# 05_MOTORS.net
KiCad netlist of a schematic drawn in Altium Designer
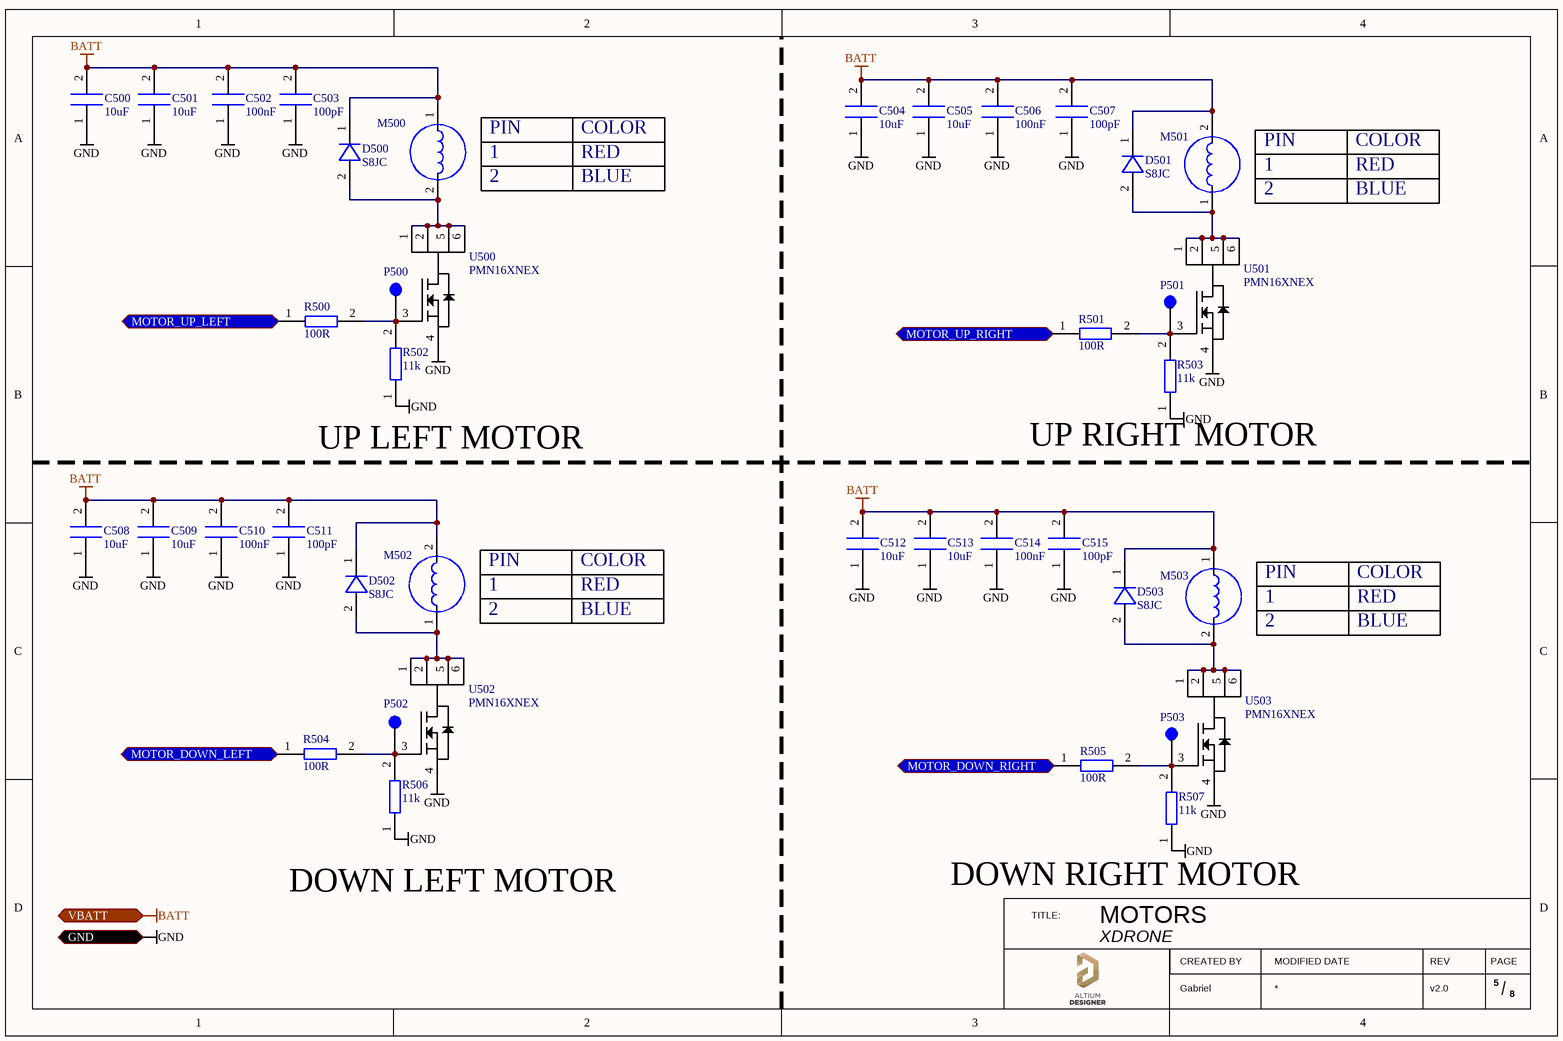
[diagram p0: 05_MOTORS.SchDoc]

(export (version "E")
  (design (tool "Eeschema 10.0.6"))
  (components
    (comp (ref "C500")
      (value "10uF")
      (footprint "CAP_0805")
      (description "CAP 10uF 10% 10V 0805 X6S")
      (fields (field (name "TOLERANCE") "10%") (field (name "MANUFACTURER") "MURATA"))
      (libsource (lib "Capacitors") (part "10uF_10%_10V_0805_X6S_GRM21BC81C106KA73L"))
    )
    (comp (ref "C501")
      (value "10uF")
      (footprint "CAP_0805")
      (description "CAP 10uF 10% 10V 0805 X6S")
      (fields (field (name "TOLERANCE") "10%") (field (name "MANUFACTURER") "MURATA"))
      (libsource (lib "Capacitors") (part "10uF_10%_10V_0805_X6S_GRM21BC81C106KA73L"))
    )
    (comp (ref "C502")
      (value "100nF")
      (footprint "CAP_0402")
      (description "CAPACITOR 100nF 10% X7R 0402")
      (fields (field (name "TOLERANCE") "10%") (field (name "MANUFACTURER") "MURATA"))
      (libsource (lib "Capacitors") (part "100nF_10%_16V_0402_GRM155R71C104KA88J"))
    )
    (comp (ref "C503")
      (value "100pF")
      (footprint "CAP_0402")
      (description "CAPACITOR 100pF 5% 50V 0402 CC0402JRNPO9BN101")
      (fields (field (name "TOLERANCE") "5%") (field (name "MANUFACTURER") "YAGEO"))
      (libsource (lib "Capacitors") (part "100pF_5%_50V_0402_CC0402JRNPO9BN101"))
    )
    (comp (ref "C504")
      (value "10uF")
      (footprint "CAP_0805")
      (description "CAP 10uF 10% 10V 0805 X6S")
      (fields (field (name "TOLERANCE") "10%") (field (name "MANUFACTURER") "MURATA"))
      (libsource (lib "Capacitors") (part "10uF_10%_10V_0805_X6S_GRM21BC81C106KA73L"))
    )
    (comp (ref "C505")
      (value "10uF")
      (footprint "CAP_0805")
      (description "CAP 10uF 10% 10V 0805 X6S")
      (fields (field (name "TOLERANCE") "10%") (field (name "MANUFACTURER") "MURATA"))
      (libsource (lib "Capacitors") (part "10uF_10%_10V_0805_X6S_GRM21BC81C106KA73L"))
    )
    (comp (ref "C506")
      (value "100nF")
      (footprint "CAP_0402")
      (description "CAPACITOR 100nF 10% X7R 0402")
      (fields (field (name "TOLERANCE") "10%") (field (name "MANUFACTURER") "MURATA"))
      (libsource (lib "Capacitors") (part "100nF_10%_16V_0402_GRM155R71C104KA88J"))
    )
    (comp (ref "C507")
      (value "100pF")
      (footprint "CAP_0402")
      (description "CAPACITOR 100pF 5% 50V 0402 CC0402JRNPO9BN101")
      (fields (field (name "TOLERANCE") "5%") (field (name "MANUFACTURER") "YAGEO"))
      (libsource (lib "Capacitors") (part "100pF_5%_50V_0402_CC0402JRNPO9BN101"))
    )
    (comp (ref "C508")
      (value "10uF")
      (footprint "CAP_0805")
      (description "CAP 10uF 10% 10V 0805 X6S")
      (fields (field (name "TOLERANCE") "10%") (field (name "MANUFACTURER") "MURATA"))
      (libsource (lib "Capacitors") (part "10uF_10%_10V_0805_X6S_GRM21BC81C106KA73L"))
    )
    (comp (ref "C509")
      (value "10uF")
      (footprint "CAP_0805")
      (description "CAP 10uF 10% 10V 0805 X6S")
      (fields (field (name "TOLERANCE") "10%") (field (name "MANUFACTURER") "MURATA"))
      (libsource (lib "Capacitors") (part "10uF_10%_10V_0805_X6S_GRM21BC81C106KA73L"))
    )
    (comp (ref "C510")
      (value "100nF")
      (footprint "CAP_0402")
      (description "CAPACITOR 100nF 10% X7R 0402")
      (fields (field (name "TOLERANCE") "10%") (field (name "MANUFACTURER") "MURATA"))
      (libsource (lib "Capacitors") (part "100nF_10%_16V_0402_GRM155R71C104KA88J"))
    )
    (comp (ref "C511")
      (value "100pF")
      (footprint "CAP_0402")
      (description "CAPACITOR 100pF 5% 50V 0402 CC0402JRNPO9BN101")
      (fields (field (name "TOLERANCE") "5%") (field (name "MANUFACTURER") "YAGEO"))
      (libsource (lib "Capacitors") (part "100pF_5%_50V_0402_CC0402JRNPO9BN101"))
    )
    (comp (ref "C512")
      (value "10uF")
      (footprint "CAP_0805")
      (description "CAP 10uF 10% 10V 0805 X6S")
      (fields (field (name "TOLERANCE") "10%") (field (name "MANUFACTURER") "MURATA"))
      (libsource (lib "Capacitors") (part "10uF_10%_10V_0805_X6S_GRM21BC81C106KA73L"))
    )
    (comp (ref "C513")
      (value "10uF")
      (footprint "CAP_0805")
      (description "CAP 10uF 10% 10V 0805 X6S")
      (fields (field (name "TOLERANCE") "10%") (field (name "MANUFACTURER") "MURATA"))
      (libsource (lib "Capacitors") (part "10uF_10%_10V_0805_X6S_GRM21BC81C106KA73L"))
    )
    (comp (ref "C514")
      (value "100nF")
      (footprint "CAP_0402")
      (description "CAPACITOR 100nF 10% X7R 0402")
      (fields (field (name "TOLERANCE") "10%") (field (name "MANUFACTURER") "MURATA"))
      (libsource (lib "Capacitors") (part "100nF_10%_16V_0402_GRM155R71C104KA88J"))
    )
    (comp (ref "C515")
      (value "100pF")
      (footprint "CAP_0402")
      (description "CAPACITOR 100pF 5% 50V 0402 CC0402JRNPO9BN101")
      (fields (field (name "TOLERANCE") "5%") (field (name "MANUFACTURER") "YAGEO"))
      (libsource (lib "Capacitors") (part "100pF_5%_50V_0402_CC0402JRNPO9BN101"))
    )
    (comp (ref "D500")
      (value "DIODE_600V_8A_1Vf_S8JC")
      (footprint "DO-214AB")
      (description "DIODE 600V 8A 1Vf S8JC")
      (fields (field (name "MANUFACTURER") "TAIWAN") (field (name "MANUFACTURER REFERENCE") "S8JC"))
      (libsource (lib "Semiconductor") (part "DIODE_600V_8A_1Vf_S8JC"))
    )
    (comp (ref "D501")
      (value "DIODE_600V_8A_1Vf_S8JC")
      (footprint "DO-214AB")
      (description "DIODE 600V 8A 1Vf S8JC")
      (fields (field (name "MANUFACTURER") "TAIWAN") (field (name "MANUFACTURER REFERENCE") "S8JC"))
      (libsource (lib "Semiconductor") (part "DIODE_600V_8A_1Vf_S8JC"))
    )
    (comp (ref "D502")
      (value "DIODE_600V_8A_1Vf_S8JC")
      (footprint "DO-214AB")
      (description "DIODE 600V 8A 1Vf S8JC")
      (fields (field (name "MANUFACTURER") "TAIWAN") (field (name "MANUFACTURER REFERENCE") "S8JC"))
      (libsource (lib "Semiconductor") (part "DIODE_600V_8A_1Vf_S8JC"))
    )
    (comp (ref "D503")
      (value "DIODE_600V_8A_1Vf_S8JC")
      (footprint "DO-214AB")
      (description "DIODE 600V 8A 1Vf S8JC")
      (fields (field (name "MANUFACTURER") "TAIWAN") (field (name "MANUFACTURER REFERENCE") "S8JC"))
      (libsource (lib "Semiconductor") (part "DIODE_600V_8A_1Vf_S8JC"))
    )
    (comp (ref "M500")
      (value "BDC_1020_3.7V_4A")
      (footprint "1020_Motor")
      (description "Brushed DC motor 3.7V")
      (fields (field (name "MANUFACTURER") "Aliexpress"))
      (libsource (lib "Motors") (part "BDC_1020_3.7V_4A"))
    )
    (comp (ref "M501")
      (value "BDC_1020_3.7V_4A")
      (footprint "1020_Motor")
      (description "Brushed DC motor 3.7V")
      (fields (field (name "MANUFACTURER") "Aliexpress"))
      (libsource (lib "Motors") (part "BDC_1020_3.7V_4A"))
    )
    (comp (ref "M502")
      (value "BDC_1020_3.7V_4A")
      (footprint "1020_Motor")
      (description "Brushed DC motor 3.7V")
      (fields (field (name "MANUFACTURER") "Aliexpress"))
      (libsource (lib "Motors") (part "BDC_1020_3.7V_4A"))
    )
    (comp (ref "M503")
      (value "BDC_1020_3.7V_4A")
      (footprint "1020_Motor")
      (description "Brushed DC motor 3.7V")
      (fields (field (name "MANUFACTURER") "Aliexpress"))
      (libsource (lib "Motors") (part "BDC_1020_3.7V_4A"))
    )
    (comp (ref "P500")
      (value "TEST_POINT_2mm")
      (footprint "TEST_POINT_2mm")
      (libsource (lib "Connectors") (part "TEST_POINT_2mm"))
    )
    (comp (ref "P501")
      (value "TEST_POINT_2mm")
      (footprint "TEST_POINT_2mm")
      (libsource (lib "Connectors") (part "TEST_POINT_2mm"))
    )
    (comp (ref "P502")
      (value "TEST_POINT_2mm")
      (footprint "TEST_POINT_2mm")
      (libsource (lib "Connectors") (part "TEST_POINT_2mm"))
    )
    (comp (ref "P503")
      (value "TEST_POINT_2mm")
      (footprint "TEST_POINT_2mm")
      (libsource (lib "Connectors") (part "TEST_POINT_2mm"))
    )
    (comp (ref "R500")
      (value "100R")
      (footprint "RES_0402")
      (description "RESISTOR 100R 1% 0402 RC0402FR-07100RL")
      (fields (field (name "TOLERANCE") "1%") (field (name "MANUFACTURER") "YAGEO"))
      (libsource (lib "Resistors") (part "RES_100R_1%_0402_RC0402FR-07100RL"))
    )
    (comp (ref "R501")
      (value "100R")
      (footprint "RES_0402")
      (description "RESISTOR 100R 1% 0402 RC0402FR-07100RL")
      (fields (field (name "TOLERANCE") "1%") (field (name "MANUFACTURER") "YAGEO"))
      (libsource (lib "Resistors") (part "RES_100R_1%_0402_RC0402FR-07100RL"))
    )
    (comp (ref "R502")
      (value "11k")
      (footprint "RES_0402")
      (description "RESISTOR 11k 5% 0402 ERJ-2GEJ113X")
      (fields (field (name "TOLERANCE") "5%") (field (name "MANUFACTURER") "PANASONIC"))
      (libsource (lib "Resistors") (part "RES_11k_5%_0402_ERJ-2GEJ113X"))
    )
    (comp (ref "R503")
      (value "11k")
      (footprint "RES_0402")
      (description "RESISTOR 11k 5% 0402 ERJ-2GEJ113X")
      (fields (field (name "TOLERANCE") "5%") (field (name "MANUFACTURER") "PANASONIC"))
      (libsource (lib "Resistors") (part "RES_11k_5%_0402_ERJ-2GEJ113X"))
    )
    (comp (ref "R504")
      (value "100R")
      (footprint "RES_0402")
      (description "RESISTOR 100R 1% 0402 RC0402FR-07100RL")
      (fields (field (name "TOLERANCE") "1%") (field (name "MANUFACTURER") "YAGEO"))
      (libsource (lib "Resistors") (part "RES_100R_1%_0402_RC0402FR-07100RL"))
    )
    (comp (ref "R505")
      (value "100R")
      (footprint "RES_0402")
      (description "RESISTOR 100R 1% 0402 RC0402FR-07100RL")
      (fields (field (name "TOLERANCE") "1%") (field (name "MANUFACTURER") "YAGEO"))
      (libsource (lib "Resistors") (part "RES_100R_1%_0402_RC0402FR-07100RL"))
    )
    (comp (ref "R506")
      (value "11k")
      (footprint "RES_0402")
      (description "RESISTOR 11k 5% 0402 ERJ-2GEJ113X")
      (fields (field (name "TOLERANCE") "5%") (field (name "MANUFACTURER") "PANASONIC"))
      (libsource (lib "Resistors") (part "RES_11k_5%_0402_ERJ-2GEJ113X"))
    )
    (comp (ref "R507")
      (value "11k")
      (footprint "RES_0402")
      (description "RESISTOR 11k 5% 0402 ERJ-2GEJ113X")
      (fields (field (name "TOLERANCE") "5%") (field (name "MANUFACTURER") "PANASONIC"))
      (libsource (lib "Resistors") (part "RES_11k_5%_0402_ERJ-2GEJ113X"))
    )
    (comp (ref "U500")
      (value "MOS_N_1G_20VDS_6.9A_0.65Vth_PMN16XNEX")
      (footprint "TSSOP-6")
      (description "MOS N 1G 20VDS 6.9A 0.65Vth PMN16XNEX")
      (fields (field (name "MANUFACTURER") "NEXPERIA") (field (name "MANUFACTURER REFERENCE") "PMN16XNEX"))
      (libsource (lib "Semiconductor") (part "MOS_N_1G_20VDS_6.9A_0.65Vth_PMN16XNEX"))
    )
    (comp (ref "U501")
      (value "MOS_N_1G_20VDS_6.9A_0.65Vth_PMN16XNEX")
      (footprint "TSSOP-6")
      (description "MOS N 1G 20VDS 6.9A 0.65Vth PMN16XNEX")
      (fields (field (name "MANUFACTURER") "NEXPERIA") (field (name "MANUFACTURER REFERENCE") "PMN16XNEX"))
      (libsource (lib "Semiconductor") (part "MOS_N_1G_20VDS_6.9A_0.65Vth_PMN16XNEX"))
    )
    (comp (ref "U502")
      (value "MOS_N_1G_20VDS_6.9A_0.65Vth_PMN16XNEX")
      (footprint "TSSOP-6")
      (description "MOS N 1G 20VDS 6.9A 0.65Vth PMN16XNEX")
      (fields (field (name "MANUFACTURER") "NEXPERIA") (field (name "MANUFACTURER REFERENCE") "PMN16XNEX"))
      (libsource (lib "Semiconductor") (part "MOS_N_1G_20VDS_6.9A_0.65Vth_PMN16XNEX"))
    )
    (comp (ref "U503")
      (value "MOS_N_1G_20VDS_6.9A_0.65Vth_PMN16XNEX")
      (footprint "TSSOP-6")
      (description "MOS N 1G 20VDS 6.9A 0.65Vth PMN16XNEX")
      (fields (field (name "MANUFACTURER") "NEXPERIA") (field (name "MANUFACTURER REFERENCE") "PMN16XNEX"))
      (libsource (lib "Semiconductor") (part "MOS_N_1G_20VDS_6.9A_0.65Vth_PMN16XNEX"))
    )
  )
  (nets
    (net (code "1") (name "/MOTOR_DOWN_LEFT") (class "Default")
      (node (ref "R504") (pin "1") (pinfunction "1_1") (pintype "passive"))
    )
    (net (code "2") (name "/MOTOR_DOWN_RIGHT") (class "Default")
      (node (ref "R505") (pin "1") (pinfunction "1_1") (pintype "passive"))
    )
    (net (code "3") (name "/MOTOR_UP_LEFT") (class "Default")
      (node (ref "R500") (pin "1") (pinfunction "1_1") (pintype "passive"))
    )
    (net (code "4") (name "/MOTOR_UP_RIGHT") (class "Default")
      (node (ref "R501") (pin "1") (pinfunction "1_1") (pintype "passive"))
    )
    (net (code "5") (name "BATT") (class "Default")
      (node (ref "C500") (pin "2") (pinfunction "2_2") (pintype "passive"))
      (node (ref "C501") (pin "2") (pinfunction "2_2") (pintype "passive"))
      (node (ref "C502") (pin "2") (pinfunction "2_2") (pintype "passive"))
      (node (ref "C503") (pin "2") (pinfunction "2_2") (pintype "passive"))
      (node (ref "C504") (pin "2") (pinfunction "2_2") (pintype "passive"))
      (node (ref "C505") (pin "2") (pinfunction "2_2") (pintype "passive"))
      (node (ref "C506") (pin "2") (pinfunction "2_2") (pintype "passive"))
      (node (ref "C507") (pin "2") (pinfunction "2_2") (pintype "passive"))
      (node (ref "C508") (pin "2") (pinfunction "2_2") (pintype "passive"))
      (node (ref "C509") (pin "2") (pinfunction "2_2") (pintype "passive"))
      (node (ref "C510") (pin "2") (pinfunction "2_2") (pintype "passive"))
      (node (ref "C511") (pin "2") (pinfunction "2_2") (pintype "passive"))
      (node (ref "C512") (pin "2") (pinfunction "2_2") (pintype "passive"))
      (node (ref "C513") (pin "2") (pinfunction "2_2") (pintype "passive"))
      (node (ref "C514") (pin "2") (pinfunction "2_2") (pintype "passive"))
      (node (ref "C515") (pin "2") (pinfunction "2_2") (pintype "passive"))
      (node (ref "D500") (pin "1") (pinfunction "1_1") (pintype "passive"))
      (node (ref "D501") (pin "1") (pinfunction "1_1") (pintype "passive"))
      (node (ref "D502") (pin "1") (pinfunction "1_1") (pintype "passive"))
      (node (ref "D503") (pin "1") (pinfunction "1_1") (pintype "passive"))
      (node (ref "M500") (pin "1") (pinfunction "1_1") (pintype "passive"))
      (node (ref "M501") (pin "2") (pinfunction "2_2") (pintype "passive"))
      (node (ref "M502") (pin "2") (pinfunction "2_2") (pintype "passive"))
      (node (ref "M503") (pin "1") (pinfunction "1_1") (pintype "passive"))
    )
    (net (code "6") (name "GND") (class "Default")
      (node (ref "C500") (pin "1") (pinfunction "1_1") (pintype "passive"))
      (node (ref "C501") (pin "1") (pinfunction "1_1") (pintype "passive"))
      (node (ref "C502") (pin "1") (pinfunction "1_1") (pintype "passive"))
      (node (ref "C503") (pin "1") (pinfunction "1_1") (pintype "passive"))
      (node (ref "C504") (pin "1") (pinfunction "1_1") (pintype "passive"))
      (node (ref "C505") (pin "1") (pinfunction "1_1") (pintype "passive"))
      (node (ref "C506") (pin "1") (pinfunction "1_1") (pintype "passive"))
      (node (ref "C507") (pin "1") (pinfunction "1_1") (pintype "passive"))
      (node (ref "C508") (pin "1") (pinfunction "1_1") (pintype "passive"))
      (node (ref "C509") (pin "1") (pinfunction "1_1") (pintype "passive"))
      (node (ref "C510") (pin "1") (pinfunction "1_1") (pintype "passive"))
      (node (ref "C511") (pin "1") (pinfunction "1_1") (pintype "passive"))
      (node (ref "C512") (pin "1") (pinfunction "1_1") (pintype "passive"))
      (node (ref "C513") (pin "1") (pinfunction "1_1") (pintype "passive"))
      (node (ref "C514") (pin "1") (pinfunction "1_1") (pintype "passive"))
      (node (ref "C515") (pin "1") (pinfunction "1_1") (pintype "passive"))
      (node (ref "R502") (pin "1") (pinfunction "1_1") (pintype "passive"))
      (node (ref "R503") (pin "1") (pinfunction "1_1") (pintype "passive"))
      (node (ref "R506") (pin "1") (pinfunction "1_1") (pintype "passive"))
      (node (ref "R507") (pin "1") (pinfunction "1_1") (pintype "passive"))
      (node (ref "U500") (pin "4") (pinfunction "4_4") (pintype "passive"))
      (node (ref "U501") (pin "4") (pinfunction "4_4") (pintype "passive"))
      (node (ref "U502") (pin "4") (pinfunction "4_4") (pintype "passive"))
      (node (ref "U503") (pin "4") (pinfunction "4_4") (pintype "passive"))
    )
    (net (code "7") (name "Net-(D500-Pad2)") (class "Default")
      (node (ref "D500") (pin "2") (pinfunction "2_2") (pintype "passive"))
      (node (ref "M500") (pin "2") (pinfunction "2_2") (pintype "passive"))
      (node (ref "U500") (pin "1") (pinfunction "1_1") (pintype "passive"))
      (node (ref "U500") (pin "2") (pinfunction "2_2") (pintype "passive"))
      (node (ref "U500") (pin "5") (pinfunction "5_5") (pintype "passive"))
      (node (ref "U500") (pin "6") (pinfunction "6_6") (pintype "passive"))
    )
    (net (code "8") (name "Net-(D501-Pad2)") (class "Default")
      (node (ref "D501") (pin "2") (pinfunction "2_2") (pintype "passive"))
      (node (ref "M501") (pin "1") (pinfunction "1_1") (pintype "passive"))
      (node (ref "U501") (pin "1") (pinfunction "1_1") (pintype "passive"))
      (node (ref "U501") (pin "2") (pinfunction "2_2") (pintype "passive"))
      (node (ref "U501") (pin "5") (pinfunction "5_5") (pintype "passive"))
      (node (ref "U501") (pin "6") (pinfunction "6_6") (pintype "passive"))
    )
    (net (code "9") (name "Net-(D502-Pad2)") (class "Default")
      (node (ref "D502") (pin "2") (pinfunction "2_2") (pintype "passive"))
      (node (ref "M502") (pin "1") (pinfunction "1_1") (pintype "passive"))
      (node (ref "U502") (pin "1") (pinfunction "1_1") (pintype "passive"))
      (node (ref "U502") (pin "2") (pinfunction "2_2") (pintype "passive"))
      (node (ref "U502") (pin "5") (pinfunction "5_5") (pintype "passive"))
      (node (ref "U502") (pin "6") (pinfunction "6_6") (pintype "passive"))
    )
    (net (code "10") (name "Net-(D503-Pad2)") (class "Default")
      (node (ref "D503") (pin "2") (pinfunction "2_2") (pintype "passive"))
      (node (ref "M503") (pin "2") (pinfunction "2_2") (pintype "passive"))
      (node (ref "U503") (pin "1") (pinfunction "1_1") (pintype "passive"))
      (node (ref "U503") (pin "2") (pinfunction "2_2") (pintype "passive"))
      (node (ref "U503") (pin "5") (pinfunction "5_5") (pintype "passive"))
      (node (ref "U503") (pin "6") (pinfunction "6_6") (pintype "passive"))
    )
    (net (code "11") (name "Net-(P500-Pad1)") (class "Default")
      (node (ref "P500") (pin "1") (pinfunction "1_1") (pintype "passive"))
      (node (ref "R500") (pin "2") (pinfunction "2_2") (pintype "passive"))
      (node (ref "R502") (pin "2") (pinfunction "2_2") (pintype "passive"))
      (node (ref "U500") (pin "3") (pinfunction "3_3") (pintype "passive"))
    )
    (net (code "12") (name "Net-(P501-Pad1)") (class "Default")
      (node (ref "P501") (pin "1") (pinfunction "1_1") (pintype "passive"))
      (node (ref "R501") (pin "2") (pinfunction "2_2") (pintype "passive"))
      (node (ref "R503") (pin "2") (pinfunction "2_2") (pintype "passive"))
      (node (ref "U501") (pin "3") (pinfunction "3_3") (pintype "passive"))
    )
    (net (code "13") (name "Net-(P502-Pad1)") (class "Default")
      (node (ref "P502") (pin "1") (pinfunction "1_1") (pintype "passive"))
      (node (ref "R504") (pin "2") (pinfunction "2_2") (pintype "passive"))
      (node (ref "R506") (pin "2") (pinfunction "2_2") (pintype "passive"))
      (node (ref "U502") (pin "3") (pinfunction "3_3") (pintype "passive"))
    )
    (net (code "14") (name "Net-(P503-Pad1)") (class "Default")
      (node (ref "P503") (pin "1") (pinfunction "1_1") (pintype "passive"))
      (node (ref "R505") (pin "2") (pinfunction "2_2") (pintype "passive"))
      (node (ref "R507") (pin "2") (pinfunction "2_2") (pintype "passive"))
      (node (ref "U503") (pin "3") (pinfunction "3_3") (pintype "passive"))
    )
  )
)
